# MemcalLong_27C.net
KiCad netlist of a schematic drawn in EAGLE
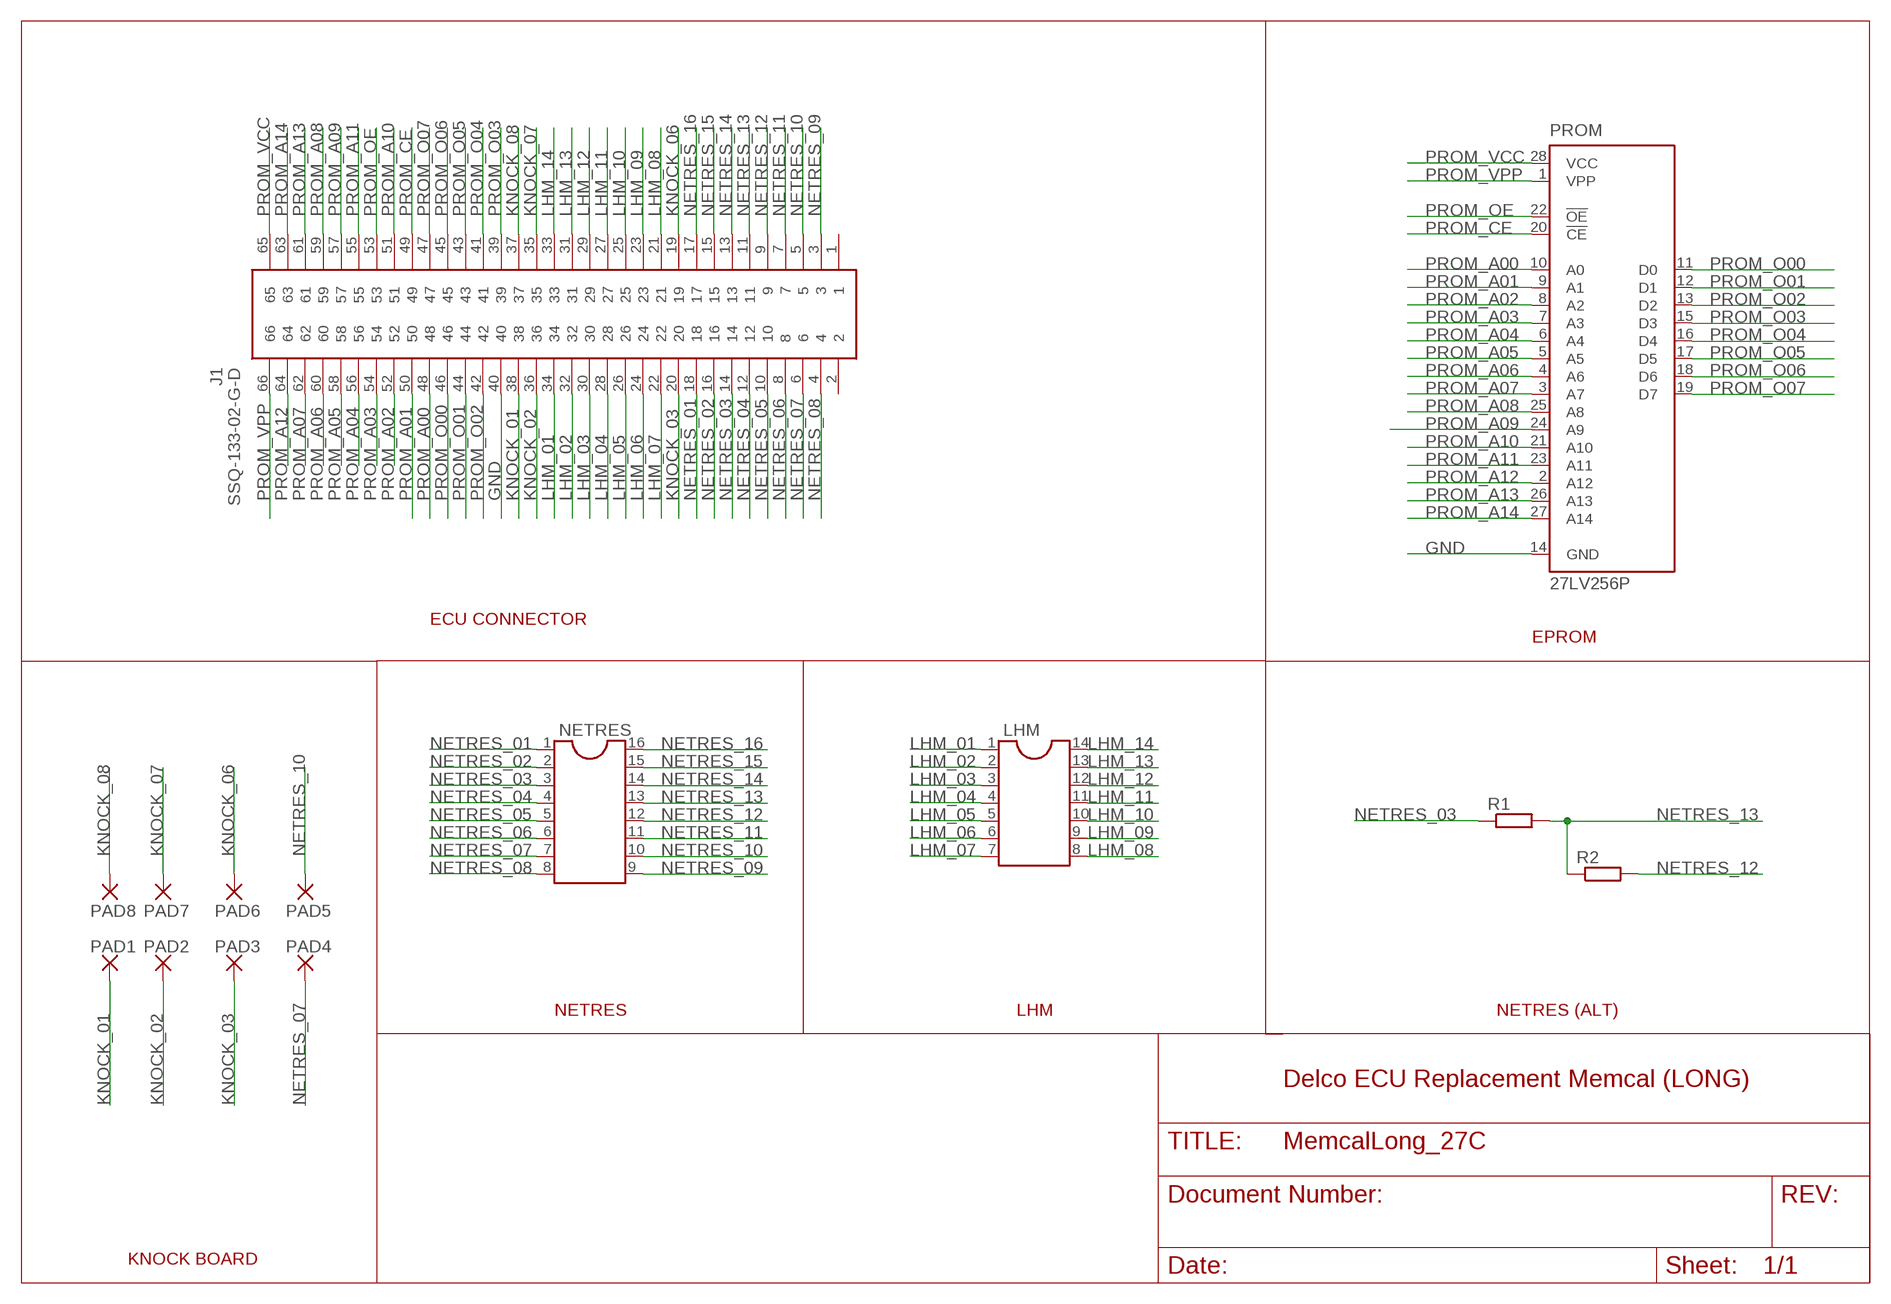
[diagram p0: schematic, sheet 1]

(export (version "E")
  (design (tool "Eeschema 10.0.6"))
  (components
    (comp (ref "J1")
      (value "SSQ-133-02-G-D")
      (footprint "eagle-import:SSQ-133-XX-YYY")
      (libsource (lib "eagle-import") (part "SSQ-133-02-G-D"))
    )
    (comp (ref "LHM")
      (value "DIL14S")
      (footprint "eagle-import:SOCKET-14")
      (libsource (lib "eagle-import") (part "DIL14S"))
    )
    (comp (ref "NETRES")
      (value "DIL16S")
      (footprint "eagle-import:SOCKET-16")
      (libsource (lib "eagle-import") (part "DIL16S"))
    )
    (comp (ref "PAD1")
      (value "SMD2")
      (footprint "eagle-import:SMD1,27-2,54")
      (libsource (lib "eagle-import") (part "SMD2"))
    )
    (comp (ref "PAD2")
      (value "SMD2")
      (footprint "eagle-import:SMD1,27-2,54")
      (libsource (lib "eagle-import") (part "SMD2"))
    )
    (comp (ref "PAD3")
      (value "SMD2")
      (footprint "eagle-import:SMD1,27-2,54")
      (libsource (lib "eagle-import") (part "SMD2"))
    )
    (comp (ref "PAD4")
      (value "SMD2")
      (footprint "eagle-import:SMD1,27-2,54")
      (libsource (lib "eagle-import") (part "SMD2"))
    )
    (comp (ref "PAD5")
      (value "SMD2")
      (footprint "eagle-import:SMD1,27-2,54")
      (libsource (lib "eagle-import") (part "SMD2"))
    )
    (comp (ref "PAD6")
      (value "SMD2")
      (footprint "eagle-import:SMD1,27-2,54")
      (libsource (lib "eagle-import") (part "SMD2"))
    )
    (comp (ref "PAD7")
      (value "SMD2")
      (footprint "eagle-import:SMD1,27-2,54")
      (libsource (lib "eagle-import") (part "SMD2"))
    )
    (comp (ref "PAD8")
      (value "SMD2")
      (footprint "eagle-import:SMD1,27-2,54")
      (libsource (lib "eagle-import") (part "SMD2"))
    )
    (comp (ref "PROM")
      (value "27LV256P")
      (footprint "eagle-import:DIL28-6")
      (libsource (lib "eagle-import") (part "27256PLV"))
    )
    (comp (ref "R1")
      (value "R-EU_0204/7")
      (footprint "eagle-import:0204_7")
      (libsource (lib "eagle-import") (part "R-EU_0204/7"))
    )
    (comp (ref "R2")
      (value "R-EU_0204/7")
      (footprint "eagle-import:0204_7")
      (libsource (lib "eagle-import") (part "R-EU_0204/7"))
    )
  )
  (nets
    (net (code "1") (name "/GND") (class "Default")
      (node (ref "J1") (pin "40") (pinfunction "40_40") (pintype "bidirectional"))
      (node (ref "PROM") (pin "14") (pinfunction "GND_14") (pintype "power_in"))
    )
    (net (code "2") (name "/KNOCK_01") (class "Default")
      (node (ref "J1") (pin "38") (pinfunction "38_38") (pintype "bidirectional"))
      (node (ref "PAD1") (pin "1") (pinfunction "P_1") (pintype "passive"))
    )
    (net (code "3") (name "/KNOCK_02") (class "Default")
      (node (ref "J1") (pin "36") (pinfunction "36_36") (pintype "bidirectional"))
      (node (ref "PAD2") (pin "1") (pinfunction "P_1") (pintype "passive"))
    )
    (net (code "4") (name "/KNOCK_03") (class "Default")
      (node (ref "J1") (pin "20") (pinfunction "20_20") (pintype "bidirectional"))
      (node (ref "PAD3") (pin "1") (pinfunction "P_1") (pintype "passive"))
    )
    (net (code "5") (name "/KNOCK_06") (class "Default")
      (node (ref "J1") (pin "19") (pinfunction "19_19") (pintype "bidirectional"))
      (node (ref "PAD6") (pin "1") (pinfunction "P_1") (pintype "passive"))
    )
    (net (code "6") (name "/KNOCK_07") (class "Default")
      (node (ref "J1") (pin "35") (pinfunction "35_35") (pintype "bidirectional"))
      (node (ref "PAD7") (pin "1") (pinfunction "P_1") (pintype "passive"))
    )
    (net (code "7") (name "/KNOCK_08") (class "Default")
      (node (ref "J1") (pin "37") (pinfunction "37_37") (pintype "bidirectional"))
      (node (ref "PAD8") (pin "1") (pinfunction "P_1") (pintype "passive"))
    )
    (net (code "8") (name "/LHM_01") (class "Default")
      (node (ref "J1") (pin "34") (pinfunction "34_34") (pintype "bidirectional"))
      (node (ref "LHM") (pin "1") (pinfunction "1_1") (pintype "passive"))
    )
    (net (code "9") (name "/LHM_02") (class "Default")
      (node (ref "J1") (pin "32") (pinfunction "32_32") (pintype "bidirectional"))
      (node (ref "LHM") (pin "2") (pinfunction "2_2") (pintype "passive"))
    )
    (net (code "10") (name "/LHM_03") (class "Default")
      (node (ref "J1") (pin "30") (pinfunction "30_30") (pintype "bidirectional"))
      (node (ref "LHM") (pin "3") (pinfunction "3_3") (pintype "passive"))
    )
    (net (code "11") (name "/LHM_04") (class "Default")
      (node (ref "J1") (pin "28") (pinfunction "28_28") (pintype "bidirectional"))
      (node (ref "LHM") (pin "4") (pinfunction "4_4") (pintype "passive"))
    )
    (net (code "12") (name "/LHM_05") (class "Default")
      (node (ref "J1") (pin "26") (pinfunction "26_26") (pintype "bidirectional"))
      (node (ref "LHM") (pin "5") (pinfunction "5_5") (pintype "passive"))
    )
    (net (code "13") (name "/LHM_06") (class "Default")
      (node (ref "J1") (pin "24") (pinfunction "24_24") (pintype "bidirectional"))
      (node (ref "LHM") (pin "6") (pinfunction "6_6") (pintype "passive"))
    )
    (net (code "14") (name "/LHM_07") (class "Default")
      (node (ref "J1") (pin "22") (pinfunction "22_22") (pintype "bidirectional"))
      (node (ref "LHM") (pin "7") (pinfunction "7_7") (pintype "passive"))
    )
    (net (code "15") (name "/LHM_08") (class "Default")
      (node (ref "J1") (pin "21") (pinfunction "21_21") (pintype "bidirectional"))
      (node (ref "LHM") (pin "8") (pinfunction "8_8") (pintype "passive"))
    )
    (net (code "16") (name "/LHM_09") (class "Default")
      (node (ref "J1") (pin "23") (pinfunction "23_23") (pintype "bidirectional"))
      (node (ref "LHM") (pin "9") (pinfunction "9_9") (pintype "passive"))
    )
    (net (code "17") (name "/LHM_10") (class "Default")
      (node (ref "J1") (pin "25") (pinfunction "25_25") (pintype "bidirectional"))
      (node (ref "LHM") (pin "10") (pinfunction "10_10") (pintype "passive"))
    )
    (net (code "18") (name "/LHM_11") (class "Default")
      (node (ref "J1") (pin "27") (pinfunction "27_27") (pintype "bidirectional"))
      (node (ref "LHM") (pin "11") (pinfunction "11_11") (pintype "passive"))
    )
    (net (code "19") (name "/LHM_12") (class "Default")
      (node (ref "J1") (pin "29") (pinfunction "29_29") (pintype "bidirectional"))
      (node (ref "LHM") (pin "12") (pinfunction "12_12") (pintype "passive"))
    )
    (net (code "20") (name "/LHM_13") (class "Default")
      (node (ref "J1") (pin "31") (pinfunction "31_31") (pintype "bidirectional"))
      (node (ref "LHM") (pin "13") (pinfunction "13_13") (pintype "passive"))
    )
    (net (code "21") (name "/LHM_14") (class "Default")
      (node (ref "J1") (pin "33") (pinfunction "33_33") (pintype "bidirectional"))
      (node (ref "LHM") (pin "14") (pinfunction "14_14") (pintype "passive"))
    )
    (net (code "22") (name "/NETRES_01") (class "Default")
      (node (ref "J1") (pin "18") (pinfunction "18_18") (pintype "bidirectional"))
      (node (ref "NETRES") (pin "1") (pinfunction "1_1") (pintype "passive"))
    )
    (net (code "23") (name "/NETRES_02") (class "Default")
      (node (ref "J1") (pin "16") (pinfunction "16_16") (pintype "bidirectional"))
      (node (ref "NETRES") (pin "2") (pinfunction "2_2") (pintype "passive"))
    )
    (net (code "24") (name "/NETRES_03") (class "Default")
      (node (ref "J1") (pin "14") (pinfunction "14_14") (pintype "bidirectional"))
      (node (ref "NETRES") (pin "3") (pinfunction "3_3") (pintype "passive"))
      (node (ref "R1") (pin "1") (pinfunction "1_1") (pintype "passive"))
    )
    (net (code "25") (name "/NETRES_04") (class "Default")
      (node (ref "J1") (pin "12") (pinfunction "12_12") (pintype "bidirectional"))
      (node (ref "NETRES") (pin "4") (pinfunction "4_4") (pintype "passive"))
    )
    (net (code "26") (name "/NETRES_05") (class "Default")
      (node (ref "J1") (pin "10") (pinfunction "10_10") (pintype "bidirectional"))
      (node (ref "NETRES") (pin "5") (pinfunction "5_5") (pintype "passive"))
    )
    (net (code "27") (name "/NETRES_06") (class "Default")
      (node (ref "J1") (pin "8") (pinfunction "8_8") (pintype "bidirectional"))
      (node (ref "NETRES") (pin "6") (pinfunction "6_6") (pintype "passive"))
    )
    (net (code "28") (name "/NETRES_07") (class "Default")
      (node (ref "J1") (pin "6") (pinfunction "6_6") (pintype "bidirectional"))
      (node (ref "NETRES") (pin "7") (pinfunction "7_7") (pintype "passive"))
      (node (ref "PAD4") (pin "1") (pinfunction "P_1") (pintype "passive"))
    )
    (net (code "29") (name "/NETRES_08") (class "Default")
      (node (ref "J1") (pin "4") (pinfunction "4_4") (pintype "bidirectional"))
      (node (ref "NETRES") (pin "8") (pinfunction "8_8") (pintype "passive"))
    )
    (net (code "30") (name "/NETRES_09") (class "Default")
      (node (ref "J1") (pin "3") (pinfunction "3_3") (pintype "bidirectional"))
      (node (ref "NETRES") (pin "9") (pinfunction "9_9") (pintype "passive"))
    )
    (net (code "31") (name "/NETRES_10") (class "Default")
      (node (ref "J1") (pin "5") (pinfunction "5_5") (pintype "bidirectional"))
      (node (ref "NETRES") (pin "10") (pinfunction "10_10") (pintype "passive"))
      (node (ref "PAD5") (pin "1") (pinfunction "P_1") (pintype "passive"))
    )
    (net (code "32") (name "/NETRES_11") (class "Default")
      (node (ref "J1") (pin "7") (pinfunction "7_7") (pintype "bidirectional"))
      (node (ref "NETRES") (pin "11") (pinfunction "11_11") (pintype "passive"))
    )
    (net (code "33") (name "/NETRES_12") (class "Default")
      (node (ref "J1") (pin "9") (pinfunction "9_9") (pintype "bidirectional"))
      (node (ref "NETRES") (pin "12") (pinfunction "12_12") (pintype "passive"))
      (node (ref "R2") (pin "2") (pinfunction "2_2") (pintype "passive"))
    )
    (net (code "34") (name "/NETRES_13") (class "Default")
      (node (ref "J1") (pin "11") (pinfunction "11_11") (pintype "bidirectional"))
      (node (ref "NETRES") (pin "13") (pinfunction "13_13") (pintype "passive"))
      (node (ref "R1") (pin "2") (pinfunction "2_2") (pintype "passive"))
      (node (ref "R2") (pin "1") (pinfunction "1_1") (pintype "passive"))
    )
    (net (code "35") (name "/NETRES_14") (class "Default")
      (node (ref "J1") (pin "13") (pinfunction "13_13") (pintype "bidirectional"))
      (node (ref "NETRES") (pin "14") (pinfunction "14_14") (pintype "passive"))
    )
    (net (code "36") (name "/NETRES_15") (class "Default")
      (node (ref "J1") (pin "15") (pinfunction "15_15") (pintype "bidirectional"))
      (node (ref "NETRES") (pin "15") (pinfunction "15_15") (pintype "passive"))
    )
    (net (code "37") (name "/NETRES_16") (class "Default")
      (node (ref "J1") (pin "17") (pinfunction "17_17") (pintype "bidirectional"))
      (node (ref "NETRES") (pin "16") (pinfunction "16_16") (pintype "passive"))
    )
    (net (code "38") (name "/PROM_A00") (class "Default")
      (node (ref "J1") (pin "48") (pinfunction "48_48") (pintype "bidirectional"))
      (node (ref "PROM") (pin "10") (pinfunction "A0_10") (pintype "input"))
    )
    (net (code "39") (name "/PROM_A01") (class "Default")
      (node (ref "J1") (pin "50") (pinfunction "50_50") (pintype "bidirectional"))
      (node (ref "PROM") (pin "9") (pinfunction "A1_9") (pintype "input"))
    )
    (net (code "40") (name "/PROM_A02") (class "Default")
      (node (ref "J1") (pin "52") (pinfunction "52_52") (pintype "bidirectional"))
      (node (ref "PROM") (pin "8") (pinfunction "A2_8") (pintype "input"))
    )
    (net (code "41") (name "/PROM_A03") (class "Default")
      (node (ref "J1") (pin "54") (pinfunction "54_54") (pintype "bidirectional"))
      (node (ref "PROM") (pin "7") (pinfunction "A3_7") (pintype "input"))
    )
    (net (code "42") (name "/PROM_A04") (class "Default")
      (node (ref "J1") (pin "56") (pinfunction "56_56") (pintype "bidirectional"))
      (node (ref "PROM") (pin "6") (pinfunction "A4_6") (pintype "input"))
    )
    (net (code "43") (name "/PROM_A05") (class "Default")
      (node (ref "J1") (pin "58") (pinfunction "58_58") (pintype "bidirectional"))
      (node (ref "PROM") (pin "5") (pinfunction "A5_5") (pintype "input"))
    )
    (net (code "44") (name "/PROM_A06") (class "Default")
      (node (ref "J1") (pin "60") (pinfunction "60_60") (pintype "bidirectional"))
      (node (ref "PROM") (pin "4") (pinfunction "A6_4") (pintype "input"))
    )
    (net (code "45") (name "/PROM_A07") (class "Default")
      (node (ref "J1") (pin "62") (pinfunction "62_62") (pintype "bidirectional"))
      (node (ref "PROM") (pin "3") (pinfunction "A7_3") (pintype "input"))
    )
    (net (code "46") (name "/PROM_A08") (class "Default")
      (node (ref "J1") (pin "59") (pinfunction "59_59") (pintype "bidirectional"))
      (node (ref "PROM") (pin "25") (pinfunction "A8_25") (pintype "input"))
    )
    (net (code "47") (name "/PROM_A09") (class "Default")
      (node (ref "J1") (pin "57") (pinfunction "57_57") (pintype "bidirectional"))
      (node (ref "PROM") (pin "24") (pinfunction "A9_24") (pintype "input"))
    )
    (net (code "48") (name "/PROM_A10") (class "Default")
      (node (ref "J1") (pin "51") (pinfunction "51_51") (pintype "bidirectional"))
      (node (ref "PROM") (pin "21") (pinfunction "A10_21") (pintype "input"))
    )
    (net (code "49") (name "/PROM_A11") (class "Default")
      (node (ref "J1") (pin "55") (pinfunction "55_55") (pintype "bidirectional"))
      (node (ref "PROM") (pin "23") (pinfunction "A11_23") (pintype "input"))
    )
    (net (code "50") (name "/PROM_A12") (class "Default")
      (node (ref "J1") (pin "64") (pinfunction "64_64") (pintype "bidirectional"))
      (node (ref "PROM") (pin "2") (pinfunction "A12_2") (pintype "input"))
    )
    (net (code "51") (name "/PROM_A13") (class "Default")
      (node (ref "J1") (pin "61") (pinfunction "61_61") (pintype "bidirectional"))
      (node (ref "PROM") (pin "26") (pinfunction "A13_26") (pintype "input"))
    )
    (net (code "52") (name "/PROM_A14") (class "Default")
      (node (ref "J1") (pin "63") (pinfunction "63_63") (pintype "bidirectional"))
      (node (ref "PROM") (pin "27") (pinfunction "A14_27") (pintype "input"))
    )
    (net (code "53") (name "/PROM_CE") (class "Default")
      (node (ref "J1") (pin "49") (pinfunction "49_49") (pintype "bidirectional"))
      (node (ref "PROM") (pin "20") (pinfunction "~{CE}_20") (pintype "input"))
    )
    (net (code "54") (name "/PROM_O00") (class "Default")
      (node (ref "J1") (pin "46") (pinfunction "46_46") (pintype "bidirectional"))
      (node (ref "PROM") (pin "11") (pinfunction "D0_11") (pintype "tri_state"))
    )
    (net (code "55") (name "/PROM_O01") (class "Default")
      (node (ref "J1") (pin "44") (pinfunction "44_44") (pintype "bidirectional"))
      (node (ref "PROM") (pin "12") (pinfunction "D1_12") (pintype "tri_state"))
    )
    (net (code "56") (name "/PROM_O02") (class "Default")
      (node (ref "J1") (pin "42") (pinfunction "42_42") (pintype "bidirectional"))
      (node (ref "PROM") (pin "13") (pinfunction "D2_13") (pintype "tri_state"))
    )
    (net (code "57") (name "/PROM_O03") (class "Default")
      (node (ref "J1") (pin "39") (pinfunction "39_39") (pintype "bidirectional"))
      (node (ref "PROM") (pin "15") (pinfunction "D3_15") (pintype "tri_state"))
    )
    (net (code "58") (name "/PROM_O04") (class "Default")
      (node (ref "J1") (pin "41") (pinfunction "41_41") (pintype "bidirectional"))
      (node (ref "PROM") (pin "16") (pinfunction "D4_16") (pintype "tri_state"))
    )
    (net (code "59") (name "/PROM_O05") (class "Default")
      (node (ref "J1") (pin "43") (pinfunction "43_43") (pintype "bidirectional"))
      (node (ref "PROM") (pin "17") (pinfunction "D5_17") (pintype "tri_state"))
    )
    (net (code "60") (name "/PROM_O06") (class "Default")
      (node (ref "J1") (pin "45") (pinfunction "45_45") (pintype "bidirectional"))
      (node (ref "PROM") (pin "18") (pinfunction "D6_18") (pintype "tri_state"))
    )
    (net (code "61") (name "/PROM_O07") (class "Default")
      (node (ref "J1") (pin "47") (pinfunction "47_47") (pintype "bidirectional"))
      (node (ref "PROM") (pin "19") (pinfunction "D7_19") (pintype "tri_state"))
    )
    (net (code "62") (name "/PROM_OE") (class "Default")
      (node (ref "J1") (pin "53") (pinfunction "53_53") (pintype "bidirectional"))
      (node (ref "PROM") (pin "22") (pinfunction "~{OE}_22") (pintype "input"))
    )
    (net (code "63") (name "/PROM_VCC") (class "Default")
      (node (ref "J1") (pin "65") (pinfunction "65_65") (pintype "bidirectional"))
      (node (ref "PROM") (pin "28") (pinfunction "VCC_28") (pintype "power_in"))
    )
    (net (code "64") (name "/PROM_VPP") (class "Default")
      (node (ref "J1") (pin "66") (pinfunction "66_66") (pintype "bidirectional"))
      (node (ref "PROM") (pin "1") (pinfunction "VPP_1") (pintype "input"))
    )
    (net (code "65") (name "unconnected-(J1-Pad1)") (class "Default")
      (node (ref "J1") (pin "1") (pinfunction "1_1") (pintype "bidirectional"))
    )
    (net (code "66") (name "unconnected-(J1-Pad2)") (class "Default")
      (node (ref "J1") (pin "2") (pinfunction "2_2") (pintype "bidirectional"))
    )
  )
)
